# Cell_Balancing.net
KiCad netlist of a schematic drawn in Altium Designer
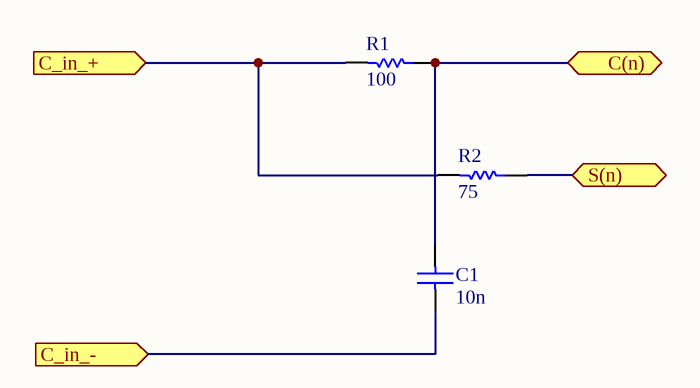
[diagram p0: Cell Balancing.SchDoc]

(export (version "E")
  (design (tool "Eeschema 10.0.6"))
  (components
    (comp (ref "C1")
      (value "10n")
      (footprint "0603 - Capacitor")
      (description "Nonpolarized Capacitor")
      (fields (field (name "Comment") "Capacitor - Nonpolarized"))
      (libsource (lib "General") (part "Capacitor - Nonpolarized"))
    )
    (comp (ref "R1")
      (value "100")
      (footprint "0805 - Resistor")
      (description "Resistor")
      (libsource (lib "General") (part "Resistor"))
    )
    (comp (ref "R2")
      (value "75")
      (footprint "0805 - Resistor")
      (description "Resistor")
      (libsource (lib "General") (part "Resistor"))
    )
  )
  (nets
    (net (code "1") (name "/C(n)") (class "Default")
      (node (ref "C1") (pin "2") (pinfunction "2_2") (pintype "passive"))
      (node (ref "R1") (pin "1") (pinfunction "1_1") (pintype "passive"))
    )
    (net (code "2") (name "/C_in_+") (class "Default")
      (node (ref "R1") (pin "2") (pinfunction "2_2") (pintype "passive"))
      (node (ref "R2") (pin "2") (pinfunction "2_2") (pintype "passive"))
    )
    (net (code "3") (name "/C_in_-") (class "Default")
      (node (ref "C1") (pin "1") (pinfunction "1_1") (pintype "passive"))
    )
    (net (code "4") (name "/S(n)") (class "Default")
      (node (ref "R2") (pin "1") (pinfunction "1_1") (pintype "passive"))
    )
  )
)
